# 2_PowerPerif.net
KiCad netlist of a schematic drawn in Altium Designer
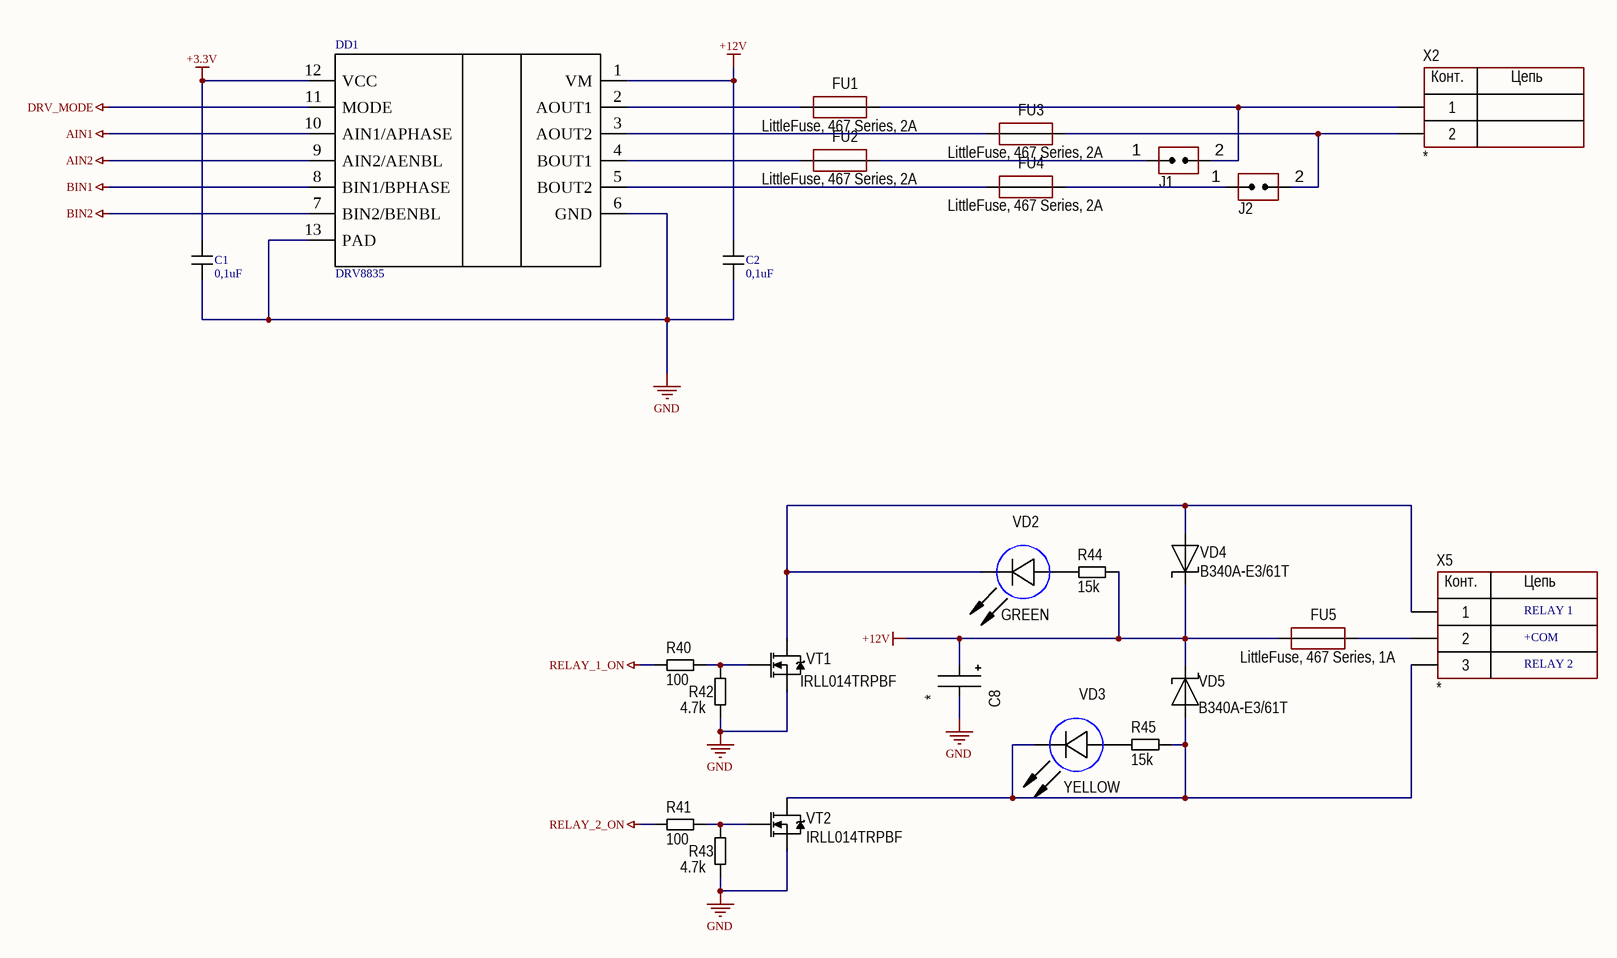
[diagram p0: 2_PowerPerif.SchDoc]

(export (version "E")
  (design (tool "Eeschema 10.0.6"))
  (components
    (comp (ref "C1") (value "0,1uF") (footprint "C_0603") (libsource (lib "Condensators") (part "C_SMD")))
    (comp (ref "C2") (value "0,1uF") (footprint "C_0603") (libsource (lib "Condensators") (part "C_SMD")))
    (comp (ref "C8") (value "*") (footprint "D8C3.2H12") (libsource (lib "Condensators") (part "AlumCap")))
    (comp (ref "DD1")
      (value "DRV8835")
      (footprint "WSON12")
      (description "Driver")
      (libsource (lib "MicroIC") (part "DRV8835"))
    )
    (comp (ref "FU1")
      (value "LittleFuse, 467 Series, 2A")
      (footprint "CH0603F")
      (libsource (lib "Melochi") (part "Fuse"))
    )
    (comp (ref "FU2")
      (value "LittleFuse, 467 Series, 2A")
      (footprint "CH0603F")
      (libsource (lib "Melochi") (part "Fuse"))
    )
    (comp (ref "FU3")
      (value "LittleFuse, 467 Series, 2A")
      (footprint "CH0603F")
      (libsource (lib "Melochi") (part "Fuse"))
    )
    (comp (ref "FU4")
      (value "LittleFuse, 467 Series, 2A")
      (footprint "CH0603F")
      (libsource (lib "Melochi") (part "Fuse"))
    )
    (comp (ref "FU5")
      (value "LittleFuse, 467 Series, 1A")
      (footprint "CH0603F")
      (libsource (lib "Melochi") (part "Fuse"))
    )
    (comp (ref "J1")
      (value "Jumper-2")
      (footprint "CON: PLS-2")
      (description "Jumper")
      (fields (field (name "MANUFACTURER") "China"))
      (libsource (lib "Connectors") (part "Jumper-2"))
    )
    (comp (ref "J2")
      (value "Jumper-2")
      (footprint "CON: PLS-2")
      (description "Jumper")
      (fields (field (name "MANUFACTURER") "China"))
      (libsource (lib "Connectors") (part "Jumper-2"))
    )
    (comp (ref "R40") (value "100") (footprint "CH0805R") (libsource (lib "Resistors") (part "Resistor")))
    (comp (ref "R41") (value "100") (footprint "CH0805R") (libsource (lib "Resistors") (part "Resistor")))
    (comp (ref "R42") (value "4.7k") (footprint "CH0805R") (libsource (lib "Resistors") (part "Resistor")))
    (comp (ref "R43") (value "4.7k") (footprint "CH0805R") (libsource (lib "Resistors") (part "Resistor")))
    (comp (ref "R44") (value "15k") (footprint "CH0805R") (libsource (lib "Resistors") (part "Resistor")))
    (comp (ref "R45") (value "15k") (footprint "CH0805R") (libsource (lib "Resistors") (part "Resistor")))
    (comp (ref "VD2") (value "GREEN") (footprint "CH0603LB") (libsource (lib "Diods") (part "LED_1")))
    (comp (ref "VD3") (value "YELLOW") (footprint "CH0603LB") (libsource (lib "Diods") (part "LED_1")))
    (comp (ref "VD4")
      (value "B340A-E3/61T")
      (footprint "SMA")
      (libsource (lib "Diods") (part "Diod Schottky"))
    )
    (comp (ref "VD5")
      (value "B340A-E3/61T")
      (footprint "SMA")
      (libsource (lib "Diods") (part "Diod Schottky"))
    )
    (comp (ref "VT1")
      (value "IRLL014TRPBF")
      (footprint "SOT223")
      (description "Mosfet")
      (libsource (lib "Tranzistor") (part "N-chanel"))
    )
    (comp (ref "VT2")
      (value "IRLL014TRPBF")
      (footprint "SOT223")
      (description "Mosfet")
      (libsource (lib "Tranzistor") (part "N-chanel"))
    )
    (comp (ref "X2") (value "*") (footprint "CON: CWF-2") (libsource (lib "Connectors") (part "2-Connector")))
    (comp (ref "X5")
      (value "*")
      (footprint "CON: 300-03P-5.0")
      (libsource (lib "Connectors") (part "3-Connector"))
    )
  )
  (nets
    (net (code "1") (name "+3.3V") (class "Default")
      (node (ref "C1") (pin "2") (pinfunction "2_2") (pintype "passive"))
      (node (ref "DD1") (pin "12") (pinfunction "VCC_12") (pintype "passive"))
    )
    (net (code "2") (name "+12V") (class "Default")
      (node (ref "C2") (pin "2") (pinfunction "2_2") (pintype "passive"))
      (node (ref "C8") (pin "1") (pinfunction "1_1") (pintype "power_in"))
      (node (ref "DD1") (pin "1") (pinfunction "VM_1") (pintype "passive"))
      (node (ref "FU5") (pin "1") (pinfunction "1_1") (pintype "passive"))
      (node (ref "R44") (pin "2") (pinfunction "2_2") (pintype "passive"))
      (node (ref "VD4") (pin "2") (pinfunction "2_2") (pintype "passive"))
      (node (ref "VD5") (pin "2") (pinfunction "2_2") (pintype "passive"))
    )
    (net (code "3") (name "AIN1") (class "Default")
      (node (ref "DD1") (pin "10") (pinfunction "AIN1/APHASE_10") (pintype "passive"))
    )
    (net (code "4") (name "AIN2") (class "Default")
      (node (ref "DD1") (pin "9") (pinfunction "AIN2/AENBL_9") (pintype "passive"))
    )
    (net (code "5") (name "BIN1") (class "Default")
      (node (ref "DD1") (pin "8") (pinfunction "BIN1/BPHASE_8") (pintype "passive"))
    )
    (net (code "6") (name "BIN2") (class "Default")
      (node (ref "DD1") (pin "7") (pinfunction "BIN2/BENBL_7") (pintype "passive"))
    )
    (net (code "7") (name "DRV_MODE") (class "Default")
      (node (ref "DD1") (pin "11") (pinfunction "MODE_11") (pintype "passive"))
    )
    (net (code "8") (name "GND") (class "Default")
      (node (ref "C1") (pin "1") (pinfunction "1_1") (pintype "passive"))
      (node (ref "C2") (pin "1") (pinfunction "1_1") (pintype "passive"))
      (node (ref "C8") (pin "2") (pinfunction "2_2") (pintype "power_in"))
      (node (ref "DD1") (pin "13") (pinfunction "PAD_13") (pintype "passive"))
      (node (ref "DD1") (pin "6") (pinfunction "GND_6") (pintype "passive"))
      (node (ref "R42") (pin "1") (pinfunction "1_1") (pintype "passive"))
      (node (ref "R43") (pin "1") (pinfunction "1_1") (pintype "passive"))
      (node (ref "VT1") (pin "3") (pinfunction "S_3") (pintype "passive"))
      (node (ref "VT2") (pin "3") (pinfunction "S_3") (pintype "passive"))
    )
    (net (code "9") (name "Net-(DD1-AOUT1)") (class "Default")
      (node (ref "DD1") (pin "2") (pinfunction "AOUT1_2") (pintype "passive"))
      (node (ref "FU1") (pin "1") (pinfunction "1_1") (pintype "passive"))
    )
    (net (code "10") (name "Net-(DD1-AOUT2)") (class "Default")
      (node (ref "DD1") (pin "3") (pinfunction "AOUT2_3") (pintype "passive"))
      (node (ref "FU3") (pin "1") (pinfunction "1_1") (pintype "passive"))
    )
    (net (code "11") (name "Net-(DD1-BOUT1)") (class "Default")
      (node (ref "DD1") (pin "4") (pinfunction "BOUT1_4") (pintype "passive"))
      (node (ref "FU2") (pin "1") (pinfunction "1_1") (pintype "passive"))
    )
    (net (code "12") (name "Net-(DD1-BOUT2)") (class "Default")
      (node (ref "DD1") (pin "5") (pinfunction "BOUT2_5") (pintype "passive"))
      (node (ref "FU4") (pin "1") (pinfunction "1_1") (pintype "passive"))
    )
    (net (code "13") (name "Net-(FU1-Pad2)") (class "Default")
      (node (ref "FU1") (pin "2") (pinfunction "2_2") (pintype "passive"))
      (node (ref "J1") (pin "2") (pinfunction "IN_2") (pintype "passive"))
      (node (ref "X2") (pin "1") (pinfunction "1_1") (pintype "passive"))
    )
    (net (code "14") (name "Net-(FU2-Pad2)") (class "Default")
      (node (ref "FU2") (pin "2") (pinfunction "2_2") (pintype "passive"))
      (node (ref "J1") (pin "1") (pinfunction "IN_1") (pintype "passive"))
    )
    (net (code "15") (name "Net-(FU3-Pad2)") (class "Default")
      (node (ref "FU3") (pin "2") (pinfunction "2_2") (pintype "passive"))
      (node (ref "J2") (pin "2") (pinfunction "IN_2") (pintype "passive"))
      (node (ref "X2") (pin "2") (pinfunction "2_2") (pintype "passive"))
    )
    (net (code "16") (name "Net-(FU4-Pad2)") (class "Default")
      (node (ref "FU4") (pin "2") (pinfunction "2_2") (pintype "passive"))
      (node (ref "J2") (pin "1") (pinfunction "IN_1") (pintype "passive"))
    )
    (net (code "17") (name "Net-(FU5-Pad2)") (class "Default")
      (node (ref "FU5") (pin "2") (pinfunction "2_2") (pintype "passive"))
      (node (ref "X5") (pin "2") (pinfunction "2_2") (pintype "passive"))
    )
    (net (code "18") (name "Net-(VD2-A)") (class "Default")
      (node (ref "R44") (pin "1") (pinfunction "1_1") (pintype "passive"))
      (node (ref "VD2") (pin "1") (pinfunction "A_1") (pintype "passive"))
    )
    (net (code "19") (name "Net-(VD2-C)") (class "Default")
      (node (ref "VD2") (pin "2") (pinfunction "C_2") (pintype "passive"))
      (node (ref "VD4") (pin "1") (pinfunction "1_1") (pintype "passive"))
      (node (ref "VT1") (pin "2") (pinfunction "D_2") (pintype "passive"))
      (node (ref "X5") (pin "1") (pinfunction "1_1") (pintype "passive"))
    )
    (net (code "20") (name "Net-(VD3-A)") (class "Default")
      (node (ref "R45") (pin "1") (pinfunction "1_1") (pintype "passive"))
      (node (ref "VD3") (pin "1") (pinfunction "A_1") (pintype "passive"))
    )
    (net (code "21") (name "Net-(VD3-C)") (class "Default")
      (node (ref "R45") (pin "2") (pinfunction "2_2") (pintype "passive"))
      (node (ref "VD3") (pin "2") (pinfunction "C_2") (pintype "passive"))
      (node (ref "VD5") (pin "1") (pinfunction "1_1") (pintype "passive"))
      (node (ref "VT2") (pin "2") (pinfunction "D_2") (pintype "passive"))
      (node (ref "X5") (pin "3") (pinfunction "3_3") (pintype "passive"))
    )
    (net (code "22") (name "Net-(VT1-G)") (class "Default")
      (node (ref "R40") (pin "1") (pinfunction "1_1") (pintype "passive"))
      (node (ref "R42") (pin "2") (pinfunction "2_2") (pintype "passive"))
      (node (ref "VT1") (pin "1") (pinfunction "G_1") (pintype "passive"))
    )
    (net (code "23") (name "Net-(VT2-G)") (class "Default")
      (node (ref "R41") (pin "1") (pinfunction "1_1") (pintype "passive"))
      (node (ref "R43") (pin "2") (pinfunction "2_2") (pintype "passive"))
      (node (ref "VT2") (pin "1") (pinfunction "G_1") (pintype "passive"))
    )
    (net (code "24") (name "RELAY_1_ON") (class "Default")
      (node (ref "R40") (pin "2") (pinfunction "2_2") (pintype "passive"))
    )
    (net (code "25") (name "RELAY_2_ON") (class "Default")
      (node (ref "R41") (pin "2") (pinfunction "2_2") (pintype "passive"))
    )
  )
)
